# Sheet1.net
KiCad netlist of a schematic drawn in Altium Designer
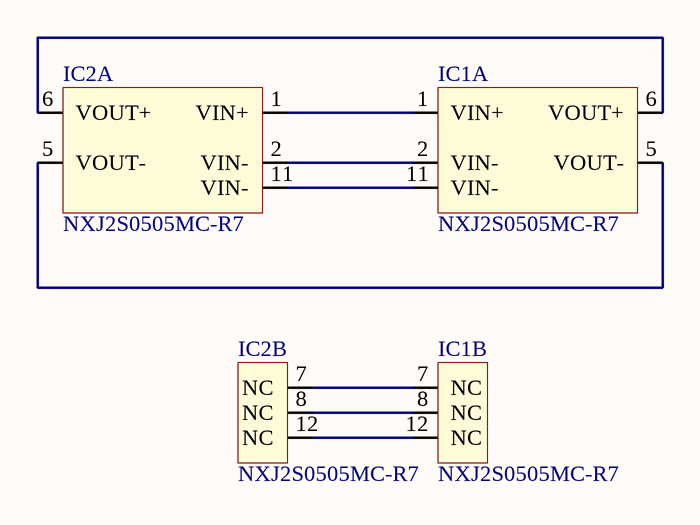
[diagram p0: Sheet1.SchDoc]

(export (version "E")
  (design (tool "Eeschema 10.0.6"))
  (components
    (comp (ref "IC1")
      (value "NXJ2S0505MC-R7")
      (footprint "DCDC")
      (description "Isolated DC/DC Converters - SMD 4.5V TO 5.5V IN 5V OUT")
      (fields (field (name "MANUFACTURER") "Murata") (field (name "CREATED FROM") "VStarost"))
      (libsource (lib "") (part "DCDC_1"))
    )
    (comp (ref "IC2")
      (value "NXJ2S0505MC-R7")
      (footprint "DCDC")
      (description "Isolated DC/DC Converters - SMD 4.5V TO 5.5V IN 5V OUT")
      (fields (field (name "MANUFACTURER") "Murata") (field (name "CREATED FROM") "VStarost"))
      (libsource (lib "user") (part "DCDC"))
    )
  )
  (nets
    (net (code "1") (name "Net-(IC1A-VIN+)") (class "Default")
      (node (ref "IC1") (pin "1") (pinfunction "VIN+_1") (pintype "passive"))
      (node (ref "IC2") (pin "1") (pinfunction "VIN+_1") (pintype "passive"))
    )
    (net (code "2") (name "Net-(IC1A-VIN--Pad2)") (class "Default")
      (node (ref "IC1") (pin "2") (pinfunction "VIN-_2") (pintype "passive"))
      (node (ref "IC2") (pin "2") (pinfunction "VIN-_2") (pintype "passive"))
    )
    (net (code "3") (name "Net-(IC1A-VIN--Pad11)") (class "Default")
      (node (ref "IC1") (pin "11") (pinfunction "VIN-_11") (pintype "passive"))
      (node (ref "IC2") (pin "11") (pinfunction "VIN-_11") (pintype "passive"))
    )
    (net (code "4") (name "Net-(IC1A-VOUT+)") (class "Default")
      (node (ref "IC1") (pin "6") (pinfunction "VOUT+_6") (pintype "passive"))
      (node (ref "IC2") (pin "6") (pinfunction "VOUT+_6") (pintype "passive"))
    )
    (net (code "5") (name "Net-(IC1A-VOUT-)") (class "Default")
      (node (ref "IC1") (pin "5") (pinfunction "VOUT-_5") (pintype "passive"))
      (node (ref "IC2") (pin "5") (pinfunction "VOUT-_5") (pintype "passive"))
    )
    (net (code "6") (name "Net-(IC1B-NC-Pad7)") (class "Default")
      (node (ref "IC1") (pin "7") (pinfunction "NC_7") (pintype "passive"))
      (node (ref "IC2") (pin "7") (pinfunction "NC_7") (pintype "passive"))
    )
    (net (code "7") (name "Net-(IC1B-NC-Pad8)") (class "Default")
      (node (ref "IC1") (pin "8") (pinfunction "NC_8") (pintype "passive"))
      (node (ref "IC2") (pin "8") (pinfunction "NC_8") (pintype "passive"))
    )
    (net (code "8") (name "Net-(IC1B-NC-Pad12)") (class "Default")
      (node (ref "IC1") (pin "12") (pinfunction "NC_12") (pintype "passive"))
      (node (ref "IC2") (pin "12") (pinfunction "NC_12") (pintype "passive"))
    )
  )
)
